# ardufocus.net
KiCad netlist of a schematic drawn in EAGLE
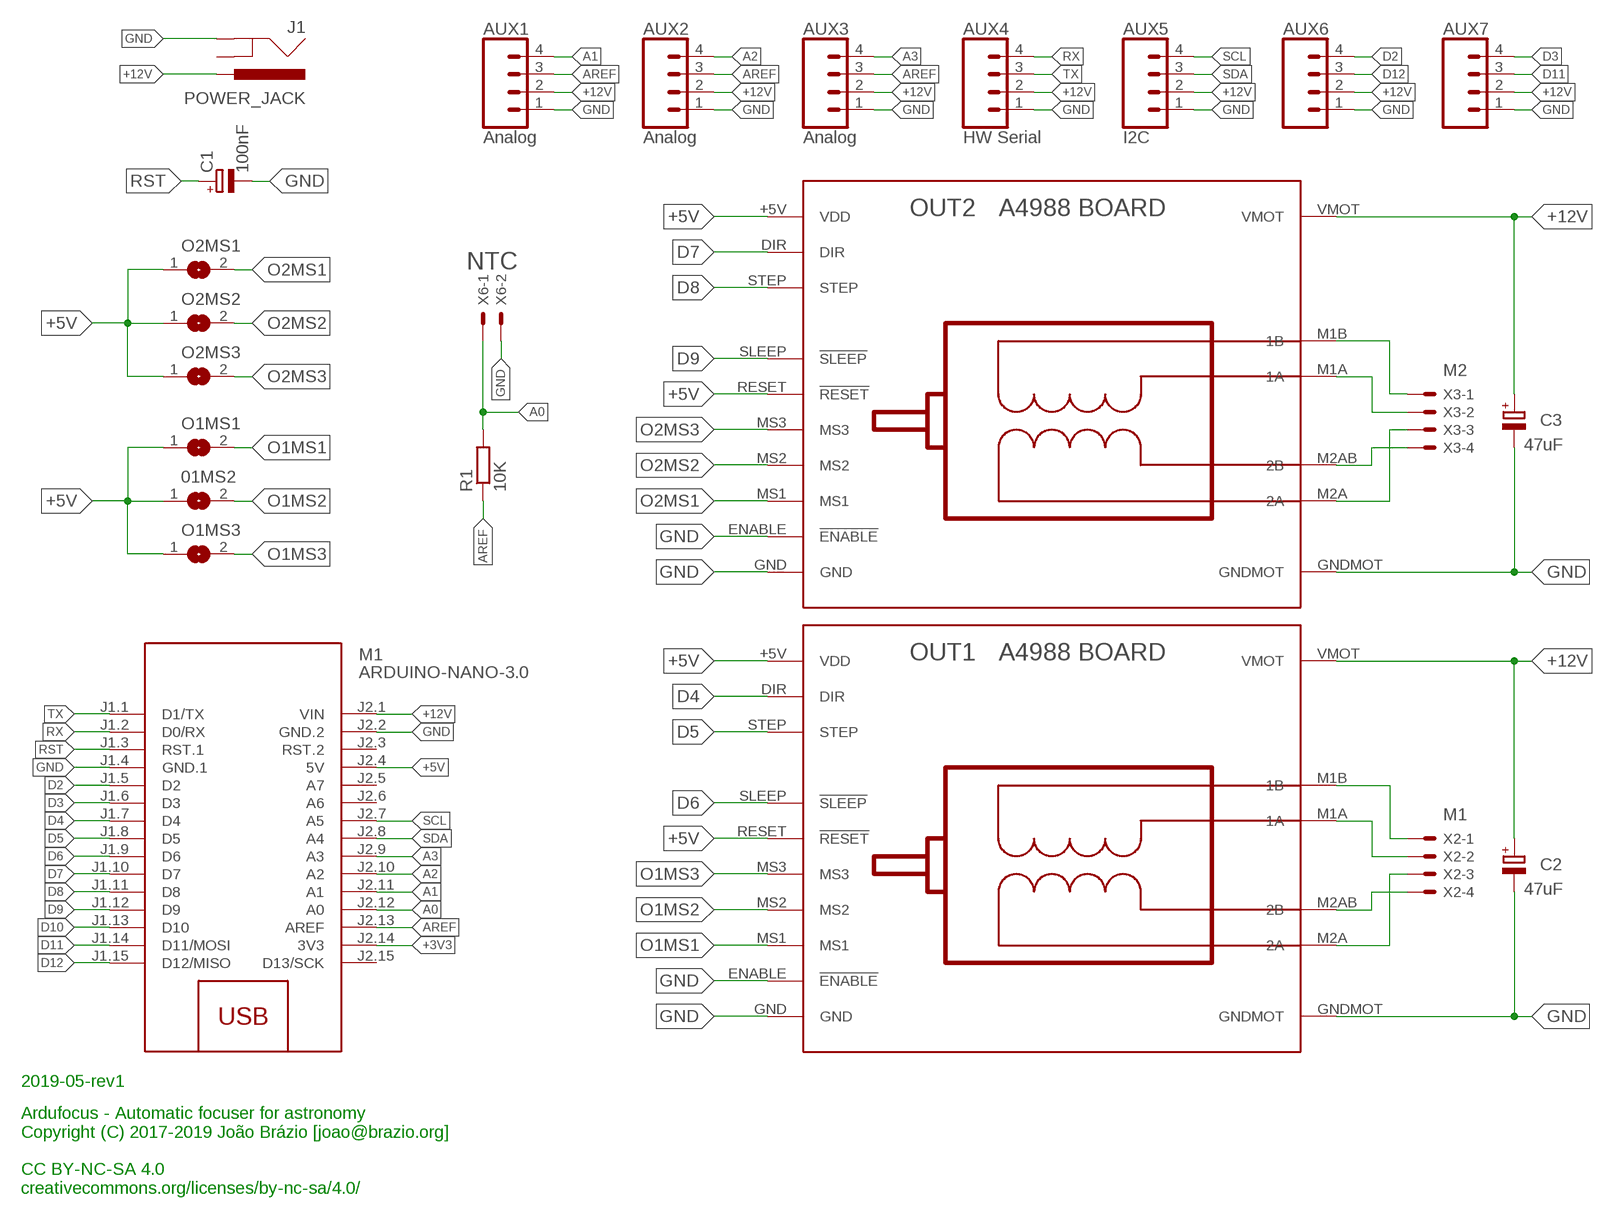
[diagram p0: schematic, sheet 1]

(export (version "E")
  (design (tool "Eeschema 10.0.6"))
  (components
    (comp (ref "01MS2")
      (value "SJ")
      (footprint "eagle-import:SJ")
      (libsource (lib "eagle-import") (part "SJ"))
    )
    (comp (ref "AUX1")
      (value "Analog")
      (footprint "eagle-import:1X04")
      (libsource (lib "eagle-import") (part "CONN_04"))
    )
    (comp (ref "AUX2")
      (value "Analog")
      (footprint "eagle-import:1X04")
      (libsource (lib "eagle-import") (part "CONN_04"))
    )
    (comp (ref "AUX3")
      (value "Analog")
      (footprint "eagle-import:1X04")
      (libsource (lib "eagle-import") (part "CONN_04"))
    )
    (comp (ref "AUX4")
      (value "HW Serial")
      (footprint "eagle-import:1X04")
      (libsource (lib "eagle-import") (part "CONN_04"))
    )
    (comp (ref "AUX5")
      (value "I2C")
      (footprint "eagle-import:1X04")
      (libsource (lib "eagle-import") (part "CONN_04"))
    )
    (comp (ref "AUX6")
      (value "CONN_04")
      (footprint "eagle-import:1X04")
      (libsource (lib "eagle-import") (part "CONN_04"))
    )
    (comp (ref "AUX7")
      (value "CONN_04")
      (footprint "eagle-import:1X04")
      (libsource (lib "eagle-import") (part "CONN_04"))
    )
    (comp (ref "C1")
      (value "100nF")
      (footprint "eagle-import:E2-5")
      (libsource (lib "eagle-import") (part "CPOL-EUE2-5"))
    )
    (comp (ref "C2")
      (value "47uF")
      (footprint "eagle-import:E3,5-8")
      (libsource (lib "eagle-import") (part "CPOL-EUE3.5-8"))
    )
    (comp (ref "C3")
      (value "47uF")
      (footprint "eagle-import:E3,5-8")
      (libsource (lib "eagle-import") (part "CPOL-EUE3.5-8"))
    )
    (comp (ref "J1")
      (value "POWER_JACK")
      (footprint "eagle-import:POWER_JACK_PTH")
      (libsource (lib "eagle-import") (part "POWER_JACK"))
    )
    (comp (ref "M1")
      (value "ARDUINO-NANO-3.0")
      (footprint "eagle-import:ARDUINO-NANO-3.0")
      (libsource (lib "eagle-import") (part "ARDUINO-NANO-3.0"))
    )
    (comp (ref "O1MS1")
      (value "SJ")
      (footprint "eagle-import:SJ")
      (libsource (lib "eagle-import") (part "SJ"))
    )
    (comp (ref "O1MS3")
      (value "SJ")
      (footprint "eagle-import:SJ")
      (libsource (lib "eagle-import") (part "SJ"))
    )
    (comp (ref "O2MS1")
      (value "SJ")
      (footprint "eagle-import:SJ")
      (libsource (lib "eagle-import") (part "SJ"))
    )
    (comp (ref "O2MS2")
      (value "SJ")
      (footprint "eagle-import:SJ")
      (libsource (lib "eagle-import") (part "SJ"))
    )
    (comp (ref "O2MS3")
      (value "SJ")
      (footprint "eagle-import:SJ")
      (libsource (lib "eagle-import") (part "SJ"))
    )
    (comp (ref "OUT1")
      (value "BOARD_A4988")
      (footprint "eagle-import:BOARD_A4988")
      (libsource (lib "eagle-import") (part "BOARD_A4988"))
    )
    (comp (ref "OUT2")
      (value "BOARD_A4988")
      (footprint "eagle-import:BOARD_A4988")
      (libsource (lib "eagle-import") (part "BOARD_A4988"))
    )
    (comp (ref "R1")
      (value "10K")
      (footprint "eagle-import:0207_7")
      (libsource (lib "eagle-import") (part "R-EU_0207/7"))
    )
    (comp (ref "X2")
      (value "JST-XH-04-PIN-LONG-PAD")
      (footprint "eagle-import:JST-XH-04-PACKAGE-LONG-PAD")
      (libsource (lib "eagle-import") (part "JST-XH-04-PIN-LONG-PAD"))
    )
    (comp (ref "X3")
      (value "JST-XH-04-PIN-LONG-PAD")
      (footprint "eagle-import:JST-XH-04-PACKAGE-LONG-PAD")
      (libsource (lib "eagle-import") (part "JST-XH-04-PIN-LONG-PAD"))
    )
    (comp (ref "X6")
      (value "JST-XH-02-PIN-LONG-PAD")
      (footprint "eagle-import:JST-XH-02-PACKAGE-LONG-PAD")
      (libsource (lib "eagle-import") (part "JST-XH-02-PIN-LONG-PAD"))
    )
  )
  (nets
    (net (code "1") (name "+3V3") (class "Default")
      (node (ref "M1") (pin "J2.14") (pinfunction "3V3_J2.14") (pintype "power_in"))
    )
    (net (code "2") (name "+5V") (class "Default")
      (node (ref "01MS2") (pin "1") (pinfunction "1_1") (pintype "passive"))
      (node (ref "M1") (pin "J2.4") (pinfunction "5V_J2.4") (pintype "power_in"))
      (node (ref "O1MS1") (pin "1") (pinfunction "1_1") (pintype "passive"))
      (node (ref "O1MS3") (pin "1") (pinfunction "1_1") (pintype "passive"))
      (node (ref "O2MS1") (pin "1") (pinfunction "1_1") (pintype "passive"))
      (node (ref "O2MS2") (pin "1") (pinfunction "1_1") (pintype "passive"))
      (node (ref "O2MS3") (pin "1") (pinfunction "1_1") (pintype "passive"))
      (node (ref "OUT1") (pin "+5V") (pinfunction "VDD_+5V") (pintype "power_in"))
      (node (ref "OUT1") (pin "RESET") (pinfunction "~{RESET}_RESET") (pintype "input"))
      (node (ref "OUT2") (pin "+5V") (pinfunction "VDD_+5V") (pintype "power_in"))
      (node (ref "OUT2") (pin "RESET") (pinfunction "~{RESET}_RESET") (pintype "input"))
    )
    (net (code "3") (name "+12V") (class "Default")
      (node (ref "AUX1") (pin "2") (pinfunction "2_2") (pintype "passive"))
      (node (ref "AUX2") (pin "2") (pinfunction "2_2") (pintype "passive"))
      (node (ref "AUX3") (pin "2") (pinfunction "2_2") (pintype "passive"))
      (node (ref "AUX4") (pin "2") (pinfunction "2_2") (pintype "passive"))
      (node (ref "AUX5") (pin "2") (pinfunction "2_2") (pintype "passive"))
      (node (ref "AUX6") (pin "2") (pinfunction "2_2") (pintype "passive"))
      (node (ref "AUX7") (pin "2") (pinfunction "2_2") (pintype "passive"))
      (node (ref "C2") (pin "+") (pinfunction "+_+") (pintype "passive"))
      (node (ref "C3") (pin "+") (pinfunction "+_+") (pintype "passive"))
      (node (ref "J1") (pin "PWR") (pinfunction "PWR_PWR") (pintype "bidirectional"))
      (node (ref "M1") (pin "J2.1") (pinfunction "VIN_J2.1") (pintype "power_in"))
      (node (ref "OUT1") (pin "VMOT") (pinfunction "VMOT_VMOT") (pintype "power_in"))
      (node (ref "OUT2") (pin "VMOT") (pinfunction "VMOT_VMOT") (pintype "power_in"))
    )
    (net (code "4") (name "A0") (class "Default")
      (node (ref "M1") (pin "J2.12") (pinfunction "A0_J2.12") (pintype "bidirectional"))
      (node (ref "R1") (pin "2") (pinfunction "2_2") (pintype "passive"))
      (node (ref "X6") (pin "1") (pinfunction "S_1") (pintype "passive"))
    )
    (net (code "5") (name "A1") (class "Default")
      (node (ref "AUX1") (pin "4") (pinfunction "4_4") (pintype "passive"))
      (node (ref "M1") (pin "J2.11") (pinfunction "A1_J2.11") (pintype "bidirectional"))
    )
    (net (code "6") (name "A2") (class "Default")
      (node (ref "AUX2") (pin "4") (pinfunction "4_4") (pintype "passive"))
      (node (ref "M1") (pin "J2.10") (pinfunction "A2_J2.10") (pintype "bidirectional"))
    )
    (net (code "7") (name "A3") (class "Default")
      (node (ref "AUX3") (pin "4") (pinfunction "4_4") (pintype "passive"))
      (node (ref "M1") (pin "J2.9") (pinfunction "A3_J2.9") (pintype "bidirectional"))
    )
    (net (code "8") (name "AREF") (class "Default")
      (node (ref "AUX1") (pin "3") (pinfunction "3_3") (pintype "passive"))
      (node (ref "AUX2") (pin "3") (pinfunction "3_3") (pintype "passive"))
      (node (ref "AUX3") (pin "3") (pinfunction "3_3") (pintype "passive"))
      (node (ref "M1") (pin "J2.13") (pinfunction "AREF_J2.13") (pintype "bidirectional"))
      (node (ref "R1") (pin "1") (pinfunction "1_1") (pintype "passive"))
    )
    (net (code "9") (name "D2") (class "Default")
      (node (ref "AUX6") (pin "4") (pinfunction "4_4") (pintype "passive"))
      (node (ref "M1") (pin "J1.5") (pinfunction "D2_J1.5") (pintype "bidirectional"))
    )
    (net (code "10") (name "D3") (class "Default")
      (node (ref "AUX7") (pin "4") (pinfunction "4_4") (pintype "passive"))
      (node (ref "M1") (pin "J1.6") (pinfunction "D3_J1.6") (pintype "bidirectional"))
    )
    (net (code "11") (name "D4") (class "Default")
      (node (ref "M1") (pin "J1.7") (pinfunction "D4_J1.7") (pintype "bidirectional"))
      (node (ref "OUT1") (pin "DIR") (pinfunction "DIR_DIR") (pintype "input"))
    )
    (net (code "12") (name "D5") (class "Default")
      (node (ref "M1") (pin "J1.8") (pinfunction "D5_J1.8") (pintype "bidirectional"))
      (node (ref "OUT1") (pin "STEP") (pinfunction "STEP_STEP") (pintype "input"))
    )
    (net (code "13") (name "D6") (class "Default")
      (node (ref "M1") (pin "J1.9") (pinfunction "D6_J1.9") (pintype "bidirectional"))
      (node (ref "OUT1") (pin "SLEEP") (pinfunction "~{SLEEP}_SLEEP") (pintype "input"))
    )
    (net (code "14") (name "D7") (class "Default")
      (node (ref "M1") (pin "J1.10") (pinfunction "D7_J1.10") (pintype "bidirectional"))
      (node (ref "OUT2") (pin "DIR") (pinfunction "DIR_DIR") (pintype "input"))
    )
    (net (code "15") (name "D8") (class "Default")
      (node (ref "M1") (pin "J1.11") (pinfunction "D8_J1.11") (pintype "bidirectional"))
      (node (ref "OUT2") (pin "STEP") (pinfunction "STEP_STEP") (pintype "input"))
    )
    (net (code "16") (name "D9") (class "Default")
      (node (ref "M1") (pin "J1.12") (pinfunction "D9_J1.12") (pintype "bidirectional"))
      (node (ref "OUT2") (pin "SLEEP") (pinfunction "~{SLEEP}_SLEEP") (pintype "input"))
    )
    (net (code "17") (name "D10") (class "Default")
      (node (ref "M1") (pin "J1.13") (pinfunction "D10_J1.13") (pintype "bidirectional"))
    )
    (net (code "18") (name "D11") (class "Default")
      (node (ref "AUX7") (pin "3") (pinfunction "3_3") (pintype "passive"))
      (node (ref "M1") (pin "J1.14") (pinfunction "D11/MOSI_J1.14") (pintype "bidirectional"))
    )
    (net (code "19") (name "D12") (class "Default")
      (node (ref "AUX6") (pin "3") (pinfunction "3_3") (pintype "passive"))
      (node (ref "M1") (pin "J1.15") (pinfunction "D12/MISO_J1.15") (pintype "bidirectional"))
    )
    (net (code "20") (name "GND") (class "Default")
      (node (ref "AUX1") (pin "1") (pinfunction "1_1") (pintype "passive"))
      (node (ref "AUX2") (pin "1") (pinfunction "1_1") (pintype "passive"))
      (node (ref "AUX3") (pin "1") (pinfunction "1_1") (pintype "passive"))
      (node (ref "AUX4") (pin "1") (pinfunction "1_1") (pintype "passive"))
      (node (ref "AUX5") (pin "1") (pinfunction "1_1") (pintype "passive"))
      (node (ref "AUX6") (pin "1") (pinfunction "1_1") (pintype "passive"))
      (node (ref "AUX7") (pin "1") (pinfunction "1_1") (pintype "passive"))
      (node (ref "C1") (pin "-") (pinfunction "-_-") (pintype "passive"))
      (node (ref "C2") (pin "-") (pinfunction "-_-") (pintype "passive"))
      (node (ref "C3") (pin "-") (pinfunction "-_-") (pintype "passive"))
      (node (ref "J1") (pin "GND") (pinfunction "GND_GND") (pintype "bidirectional"))
      (node (ref "M1") (pin "J1.4") (pinfunction "GND.1_J1.4") (pintype "power_in"))
      (node (ref "M1") (pin "J2.2") (pinfunction "GND.2_J2.2") (pintype "power_in"))
      (node (ref "OUT1") (pin "ENABLE") (pinfunction "~{ENABLE}_ENABLE") (pintype "input"))
      (node (ref "OUT1") (pin "GND") (pinfunction "GND_GND") (pintype "power_in"))
      (node (ref "OUT1") (pin "GNDMOT") (pinfunction "GNDMOT_GNDMOT") (pintype "power_in"))
      (node (ref "OUT2") (pin "ENABLE") (pinfunction "~{ENABLE}_ENABLE") (pintype "input"))
      (node (ref "OUT2") (pin "GND") (pinfunction "GND_GND") (pintype "power_in"))
      (node (ref "OUT2") (pin "GNDMOT") (pinfunction "GNDMOT_GNDMOT") (pintype "power_in"))
      (node (ref "X6") (pin "2") (pinfunction "S_2") (pintype "passive"))
    )
    (net (code "21") (name "Net-(OUT1-1A)") (class "Default")
      (node (ref "OUT1") (pin "M1A") (pinfunction "1A_M1A") (pintype "output"))
      (node (ref "X2") (pin "2") (pinfunction "S_2") (pintype "passive"))
    )
    (net (code "22") (name "Net-(OUT1-1B)") (class "Default")
      (node (ref "OUT1") (pin "M1B") (pinfunction "1B_M1B") (pintype "output"))
      (node (ref "X2") (pin "1") (pinfunction "S_1") (pintype "passive"))
    )
    (net (code "23") (name "Net-(OUT1-2A)") (class "Default")
      (node (ref "OUT1") (pin "M2A") (pinfunction "2A_M2A") (pintype "output"))
      (node (ref "X2") (pin "3") (pinfunction "S_3") (pintype "passive"))
    )
    (net (code "24") (name "Net-(OUT1-2B)") (class "Default")
      (node (ref "OUT1") (pin "M2AB") (pinfunction "2B_M2AB") (pintype "output"))
      (node (ref "X2") (pin "4") (pinfunction "S_4") (pintype "passive"))
    )
    (net (code "25") (name "Net-(OUT2-1A)") (class "Default")
      (node (ref "OUT2") (pin "M1A") (pinfunction "1A_M1A") (pintype "output"))
      (node (ref "X3") (pin "2") (pinfunction "S_2") (pintype "passive"))
    )
    (net (code "26") (name "Net-(OUT2-1B)") (class "Default")
      (node (ref "OUT2") (pin "M1B") (pinfunction "1B_M1B") (pintype "output"))
      (node (ref "X3") (pin "1") (pinfunction "S_1") (pintype "passive"))
    )
    (net (code "27") (name "Net-(OUT2-2A)") (class "Default")
      (node (ref "OUT2") (pin "M2A") (pinfunction "2A_M2A") (pintype "output"))
      (node (ref "X3") (pin "3") (pinfunction "S_3") (pintype "passive"))
    )
    (net (code "28") (name "Net-(OUT2-2B)") (class "Default")
      (node (ref "OUT2") (pin "M2AB") (pinfunction "2B_M2AB") (pintype "output"))
      (node (ref "X3") (pin "4") (pinfunction "S_4") (pintype "passive"))
    )
    (net (code "29") (name "O1MS1") (class "Default")
      (node (ref "O1MS1") (pin "2") (pinfunction "2_2") (pintype "passive"))
      (node (ref "OUT1") (pin "MS1") (pinfunction "MS1_MS1") (pintype "input"))
    )
    (net (code "30") (name "O1MS2") (class "Default")
      (node (ref "01MS2") (pin "2") (pinfunction "2_2") (pintype "passive"))
      (node (ref "OUT1") (pin "MS2") (pinfunction "MS2_MS2") (pintype "input"))
    )
    (net (code "31") (name "O1MS3") (class "Default")
      (node (ref "O1MS3") (pin "2") (pinfunction "2_2") (pintype "passive"))
      (node (ref "OUT1") (pin "MS3") (pinfunction "MS3_MS3") (pintype "input"))
    )
    (net (code "32") (name "O2MS1") (class "Default")
      (node (ref "O2MS1") (pin "2") (pinfunction "2_2") (pintype "passive"))
      (node (ref "OUT2") (pin "MS1") (pinfunction "MS1_MS1") (pintype "input"))
    )
    (net (code "33") (name "O2MS2") (class "Default")
      (node (ref "O2MS2") (pin "2") (pinfunction "2_2") (pintype "passive"))
      (node (ref "OUT2") (pin "MS2") (pinfunction "MS2_MS2") (pintype "input"))
    )
    (net (code "34") (name "O2MS3") (class "Default")
      (node (ref "O2MS3") (pin "2") (pinfunction "2_2") (pintype "passive"))
      (node (ref "OUT2") (pin "MS3") (pinfunction "MS3_MS3") (pintype "input"))
    )
    (net (code "35") (name "RST") (class "Default")
      (node (ref "C1") (pin "+") (pinfunction "+_+") (pintype "passive"))
      (node (ref "M1") (pin "J1.3") (pinfunction "RST.1_J1.3") (pintype "bidirectional"))
    )
    (net (code "36") (name "RX") (class "Default")
      (node (ref "AUX4") (pin "4") (pinfunction "4_4") (pintype "passive"))
      (node (ref "M1") (pin "J1.2") (pinfunction "D0/RX_J1.2") (pintype "bidirectional"))
    )
    (net (code "37") (name "SCL") (class "Default")
      (node (ref "AUX5") (pin "4") (pinfunction "4_4") (pintype "passive"))
      (node (ref "M1") (pin "J2.7") (pinfunction "A5_J2.7") (pintype "bidirectional"))
    )
    (net (code "38") (name "SDA") (class "Default")
      (node (ref "AUX5") (pin "3") (pinfunction "3_3") (pintype "passive"))
      (node (ref "M1") (pin "J2.8") (pinfunction "A4_J2.8") (pintype "bidirectional"))
    )
    (net (code "39") (name "TX") (class "Default")
      (node (ref "AUX4") (pin "3") (pinfunction "3_3") (pintype "passive"))
      (node (ref "M1") (pin "J1.1") (pinfunction "D1/TX_J1.1") (pintype "bidirectional"))
    )
    (net (code "40") (name "unconnected-(J1-PadGNDBREAK)") (class "Default")
      (node (ref "J1") (pin "GNDBREAK") (pinfunction "GNDBREAK_GNDBREAK") (pintype "bidirectional"))
    )
    (net (code "41") (name "unconnected-(M1-A6-PadJ2.6)") (class "Default")
      (node (ref "M1") (pin "J2.6") (pinfunction "A6_J2.6") (pintype "bidirectional"))
    )
    (net (code "42") (name "unconnected-(M1-A7-PadJ2.5)") (class "Default")
      (node (ref "M1") (pin "J2.5") (pinfunction "A7_J2.5") (pintype "bidirectional"))
    )
    (net (code "43") (name "unconnected-(M1-D13{slash}SCK-PadJ2.15)") (class "Default")
      (node (ref "M1") (pin "J2.15") (pinfunction "D13/SCK_J2.15") (pintype "bidirectional"))
    )
    (net (code "44") (name "unconnected-(M1-RST.2-PadJ2.3)") (class "Default")
      (node (ref "M1") (pin "J2.3") (pinfunction "RST.2_J2.3") (pintype "bidirectional"))
    )
  )
)
